# Switch_P.net
KiCad netlist of a schematic drawn in EAGLE
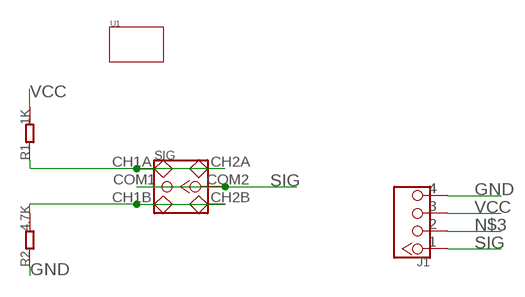
[diagram p0: schematic, sheet 1]

(export (version "E")
  (design (tool "Eeschema 10.0.6"))
  (components
    (comp (ref "J1")
      (value "TWIG-4P-2.0-2.0")
      (footprint "eagle-import:4P-2.0")
      (libsource (lib "eagle-import") (part "TWIG-4P-2.0-2.0"))
    )
    (comp (ref "R1")
      (value "1K")
      (footprint "eagle-import:0603")
      (libsource (lib "eagle-import") (part "R-0603"))
    )
    (comp (ref "R2")
      (value "4.7K")
      (footprint "eagle-import:0603")
      (libsource (lib "eagle-import") (part "R-0603"))
    )
    (comp (ref "SIG")
      (value "SWITCH-2CH-6P")
      (footprint "eagle-import:6P-2CH-2.54-7.6X3.0")
      (libsource (lib "eagle-import") (part "SWITCH-2CH-6P"))
    )
    (comp (ref "U1")
      (value "TWIG-1U")
      (footprint "eagle-import:1U-DIM-W_-DRILL")
      (libsource (lib "eagle-import") (part "TWIG-1U"))
    )
  )
  (nets
    (net (code "1") (name "/GND") (class "Default")
      (node (ref "J1") (pin "4") (pinfunction "4_4") (pintype "bidirectional"))
      (node (ref "R2") (pin "1") (pinfunction "1_1") (pintype "passive"))
    )
    (net (code "2") (name "/N$3") (class "Default")
      (node (ref "J1") (pin "2") (pinfunction "2_2") (pintype "bidirectional"))
    )
    (net (code "3") (name "/SIG") (class "Default")
      (node (ref "J1") (pin "1") (pinfunction "1_1") (pintype "bidirectional"))
      (node (ref "SIG") (pin "COM1") (pinfunction "COM1_COM1") (pintype "bidirectional"))
      (node (ref "SIG") (pin "COM2") (pinfunction "COM2_COM2") (pintype "bidirectional"))
    )
    (net (code "4") (name "/VCC") (class "Default")
      (node (ref "J1") (pin "3") (pinfunction "3_3") (pintype "bidirectional"))
      (node (ref "R1") (pin "2") (pinfunction "2_2") (pintype "passive"))
    )
    (net (code "5") (name "Net-(R1-Pad1)") (class "Default")
      (node (ref "R1") (pin "1") (pinfunction "1_1") (pintype "passive"))
      (node (ref "SIG") (pin "CH1A") (pinfunction "CH1A_CH1A") (pintype "bidirectional"))
      (node (ref "SIG") (pin "CH2A") (pinfunction "CH2A_CH2A") (pintype "bidirectional"))
    )
    (net (code "6") (name "Net-(R2-Pad2)") (class "Default")
      (node (ref "R2") (pin "2") (pinfunction "2_2") (pintype "passive"))
      (node (ref "SIG") (pin "CH1B") (pinfunction "CH1B_CH1B") (pintype "bidirectional"))
      (node (ref "SIG") (pin "CH2B") (pinfunction "CH2B_CH2B") (pintype "bidirectional"))
    )
  )
)
